# Mechanical.net
KiCad netlist of a schematic drawn in Altium Designer
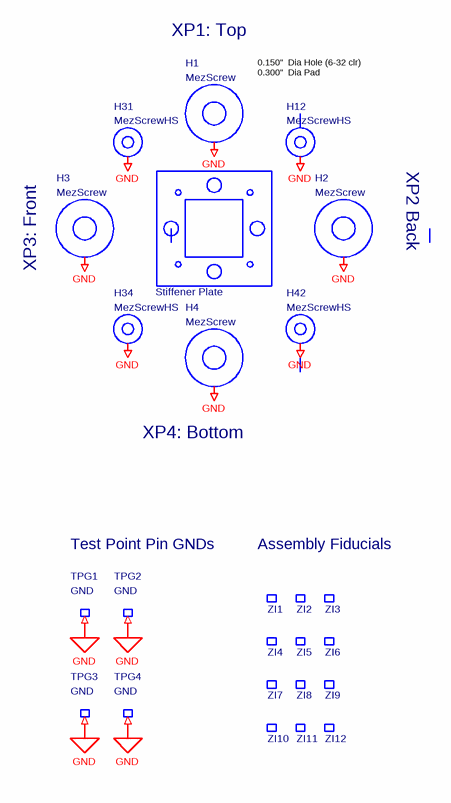
[diagram p0: Mechanical.SchDoc]

(export (version "E")
  (design (tool "Eeschema 10.0.6"))
  (components
    (comp (ref "H1")
      (value "MezScrew")
      (footprint "MC_S6/TH/SCREW_BASE")
      (libsource (lib "ALCT_MEZ_SPARTAN6_Library") (part "MezScrew"))
    )
    (comp (ref "H2")
      (value "MezScrew")
      (footprint "MC_S6/TH/SCREW_BASE")
      (libsource (lib "ALCT_MEZ_SPARTAN6_Library") (part "MezScrew"))
    )
    (comp (ref "H3")
      (value "MezScrew")
      (footprint "MC_S6/TH/SCREW_BASE")
      (libsource (lib "ALCT_MEZ_SPARTAN6_Library") (part "MezScrew"))
    )
    (comp (ref "H4")
      (value "MezScrew")
      (footprint "MC_S6/TH/SCREW_BASE")
      (libsource (lib "ALCT_MEZ_SPARTAN6_Library") (part "MezScrew"))
    )
    (comp (ref "H12")
      (value "MezScrewHS")
      (footprint "MC_S6/TH/SCREW_PLATE")
      (libsource (lib "ALCT_MEZ_SPARTAN6_Library") (part "MezScrewHS"))
    )
    (comp (ref "H31")
      (value "MezScrewHS")
      (footprint "MC_S6/TH/SCREW_PLATE")
      (libsource (lib "ALCT_MEZ_SPARTAN6_Library") (part "MezScrewHS"))
    )
    (comp (ref "H34")
      (value "MezScrewHS")
      (footprint "MC_S6/TH/SCREW_PLATE")
      (libsource (lib "ALCT_MEZ_SPARTAN6_Library") (part "MezScrewHS"))
    )
    (comp (ref "H42")
      (value "MezScrewHS")
      (footprint "MC_S6/TH/SCREW_PLATE")
      (libsource (lib "ALCT_MEZ_SPARTAN6_Library") (part "MezScrewHS"))
    )
    (comp (ref "SP1")
      (value "Stiffener Plate")
      (footprint "MC_S6/SPLATE")
      (libsource (lib "ALCT_MEZ_SPARTAN6_Library") (part "SPlate_MC_S6"))
    )
    (comp (ref "TPG1") (value "GND") (footprint "MC_S6/TH/TPGND") (libsource (lib "*") (part "TPGND")))
    (comp (ref "TPG2") (value "GND") (footprint "MC_S6/TH/TPGND") (libsource (lib "*") (part "TPGND")))
    (comp (ref "TPG3") (value "GND") (footprint "MC_S6/TH/TPGND") (libsource (lib "*") (part "TPGND")))
    (comp (ref "TPG4") (value "GND") (footprint "MC_S6/TH/TPGND") (libsource (lib "*") (part "TPGND")))
    (comp (ref "ZI1")
      (value "Fiducial Dot")
      (footprint "MC_S6/SM/FIDUCIAL_DOT")
      (libsource (lib "ALCT_MEZ_SPARTAN6_Library") (part "Fiducial_dot"))
    )
    (comp (ref "ZI2")
      (value "Fiducial Dot")
      (footprint "MC_S6/SM/FIDUCIAL_DOT")
      (libsource (lib "ALCT_MEZ_SPARTAN6_Library") (part "Fiducial_dot"))
    )
    (comp (ref "ZI3")
      (value "Fiducial Dot")
      (footprint "MC_S6/SM/FIDUCIAL_DOT")
      (libsource (lib "ALCT_MEZ_SPARTAN6_Library") (part "Fiducial_dot"))
    )
    (comp (ref "ZI4")
      (value "Fiducial Dot")
      (footprint "MC_S6/SM/FIDUCIAL_DOT")
      (libsource (lib "ALCT_MEZ_SPARTAN6_Library") (part "Fiducial_dot"))
    )
    (comp (ref "ZI5")
      (value "Fiducial Dot")
      (footprint "MC_S6/SM/FIDUCIAL_DOT")
      (libsource (lib "ALCT_MEZ_SPARTAN6_Library") (part "Fiducial_dot"))
    )
    (comp (ref "ZI6")
      (value "Fiducial Dot")
      (footprint "MC_S6/SM/FIDUCIAL_DOT")
      (libsource (lib "ALCT_MEZ_SPARTAN6_Library") (part "Fiducial_dot"))
    )
    (comp (ref "ZI7")
      (value "Fiducial Dot")
      (footprint "MC_S6/SM/FIDUCIAL_DOT")
      (libsource (lib "ALCT_MEZ_SPARTAN6_Library") (part "Fiducial_dot"))
    )
    (comp (ref "ZI8")
      (value "Fiducial Dot")
      (footprint "MC_S6/SM/FIDUCIAL_DOT")
      (libsource (lib "ALCT_MEZ_SPARTAN6_Library") (part "Fiducial_dot"))
    )
    (comp (ref "ZI9")
      (value "Fiducial Dot")
      (footprint "MC_S6/SM/FIDUCIAL_DOT")
      (libsource (lib "ALCT_MEZ_SPARTAN6_Library") (part "Fiducial_dot"))
    )
    (comp (ref "ZI10")
      (value "Fiducial Dot")
      (footprint "MC_S6/SM/FIDUCIAL_DOT")
      (libsource (lib "ALCT_MEZ_SPARTAN6_Library") (part "Fiducial_dot"))
    )
    (comp (ref "ZI11")
      (value "Fiducial Dot")
      (footprint "MC_S6/SM/FIDUCIAL_DOT")
      (libsource (lib "ALCT_MEZ_SPARTAN6_Library") (part "Fiducial_dot"))
    )
    (comp (ref "ZI12")
      (value "Fiducial Dot")
      (footprint "MC_S6/SM/FIDUCIAL_DOT")
      (libsource (lib "ALCT_MEZ_SPARTAN6_Library") (part "Fiducial_dot"))
    )
  )
  (nets
    (net (code "1") (name "GND") (class "Default")
      (node (ref "H1") (pin "1") (pinfunction "GND_1") (pintype "power_in"))
      (node (ref "H12") (pin "1") (pinfunction "GND_1") (pintype "power_in"))
      (node (ref "H2") (pin "1") (pinfunction "GND_1") (pintype "power_in"))
      (node (ref "H3") (pin "1") (pinfunction "GND_1") (pintype "power_in"))
      (node (ref "H31") (pin "1") (pinfunction "GND_1") (pintype "power_in"))
      (node (ref "H34") (pin "1") (pinfunction "GND_1") (pintype "power_in"))
      (node (ref "H4") (pin "1") (pinfunction "GND_1") (pintype "power_in"))
      (node (ref "H42") (pin "1") (pinfunction "GND_1") (pintype "power_in"))
      (node (ref "TPG1") (pin "1") (pinfunction "In_1") (pintype "input"))
      (node (ref "TPG2") (pin "1") (pinfunction "In_1") (pintype "input"))
      (node (ref "TPG3") (pin "1") (pinfunction "In_1") (pintype "input"))
      (node (ref "TPG4") (pin "1") (pinfunction "In_1") (pintype "input"))
    )
    (net (code "2") (name "unconnected-(ZI1-NC-Pad1)") (class "Default")
      (node (ref "ZI1") (pin "1") (pinfunction "NC_1") (pintype "passive"))
    )
    (net (code "3") (name "unconnected-(ZI2-NC-Pad1)") (class "Default")
      (node (ref "ZI2") (pin "1") (pinfunction "NC_1") (pintype "passive"))
    )
    (net (code "4") (name "unconnected-(ZI3-NC-Pad1)") (class "Default")
      (node (ref "ZI3") (pin "1") (pinfunction "NC_1") (pintype "passive"))
    )
    (net (code "5") (name "unconnected-(ZI4-NC-Pad1)") (class "Default")
      (node (ref "ZI4") (pin "1") (pinfunction "NC_1") (pintype "passive"))
    )
    (net (code "6") (name "unconnected-(ZI5-NC-Pad1)") (class "Default")
      (node (ref "ZI5") (pin "1") (pinfunction "NC_1") (pintype "passive"))
    )
    (net (code "7") (name "unconnected-(ZI6-NC-Pad1)") (class "Default")
      (node (ref "ZI6") (pin "1") (pinfunction "NC_1") (pintype "passive"))
    )
    (net (code "8") (name "unconnected-(ZI7-NC-Pad1)") (class "Default")
      (node (ref "ZI7") (pin "1") (pinfunction "NC_1") (pintype "passive"))
    )
    (net (code "9") (name "unconnected-(ZI8-NC-Pad1)") (class "Default")
      (node (ref "ZI8") (pin "1") (pinfunction "NC_1") (pintype "passive"))
    )
    (net (code "10") (name "unconnected-(ZI9-NC-Pad1)") (class "Default")
      (node (ref "ZI9") (pin "1") (pinfunction "NC_1") (pintype "passive"))
    )
    (net (code "11") (name "unconnected-(ZI10-NC-Pad1)") (class "Default")
      (node (ref "ZI10") (pin "1") (pinfunction "NC_1") (pintype "passive"))
    )
    (net (code "12") (name "unconnected-(ZI11-NC-Pad1)") (class "Default")
      (node (ref "ZI11") (pin "1") (pinfunction "NC_1") (pintype "passive"))
    )
    (net (code "13") (name "unconnected-(ZI12-NC-Pad1)") (class "Default")
      (node (ref "ZI12") (pin "1") (pinfunction "NC_1") (pintype "passive"))
    )
  )
)
